# SDIO_WIFI.net
KiCad netlist of a schematic drawn in Altium Designer
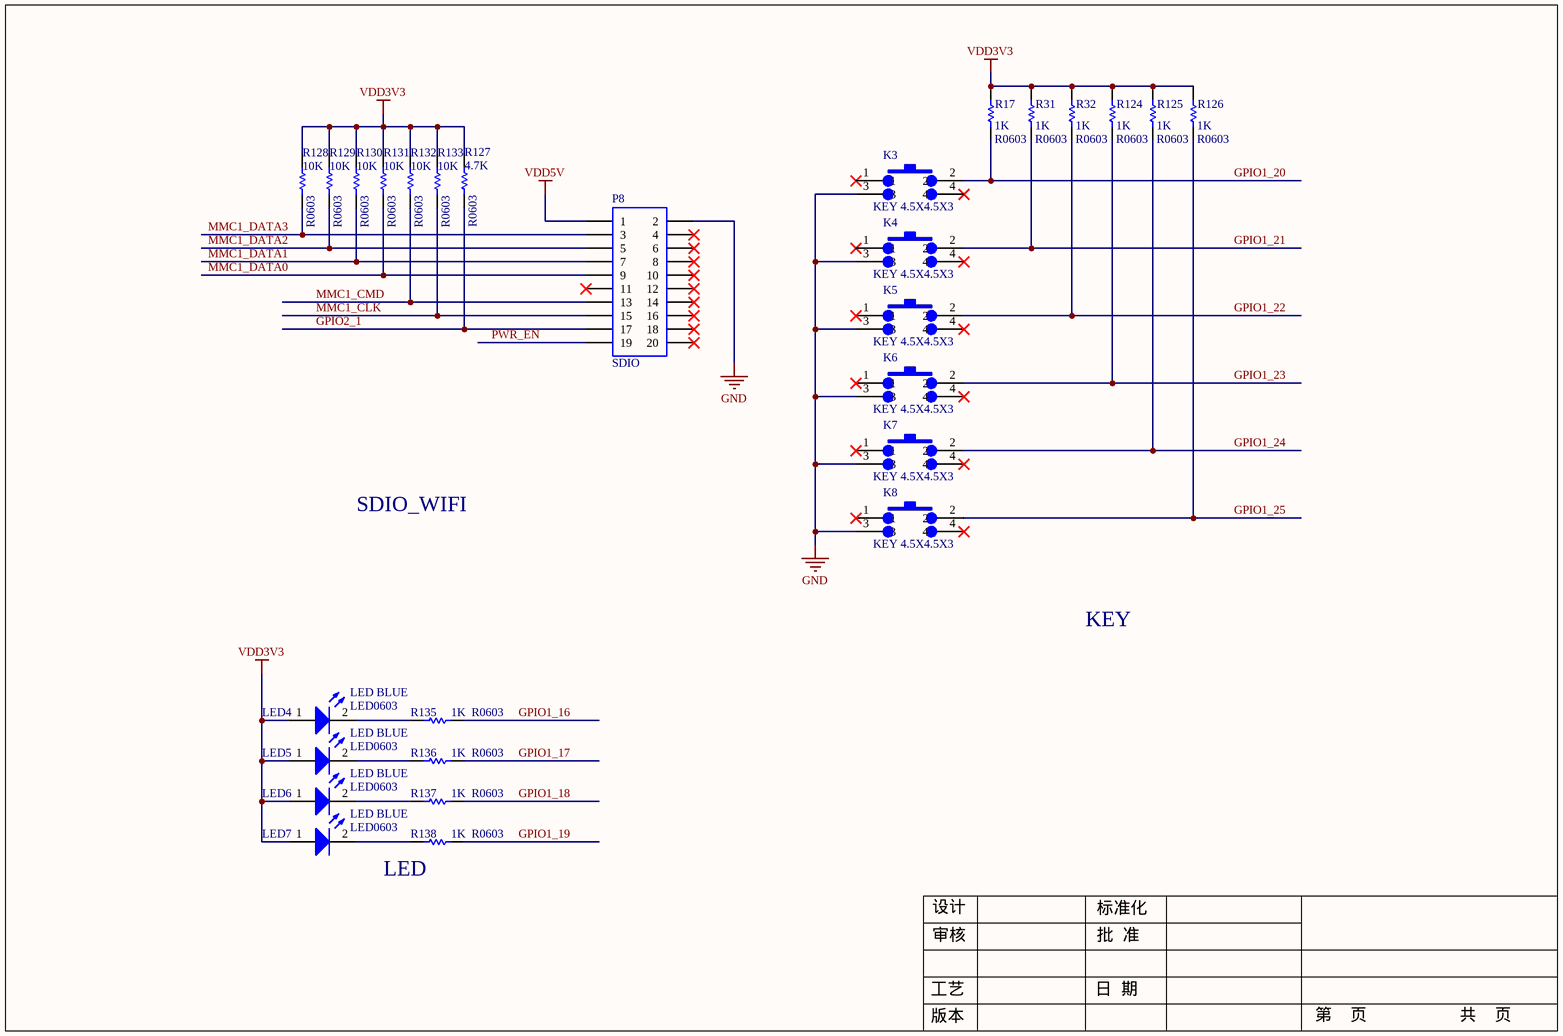
[diagram p0: SDIO_WIFI.SchDoc]

(export (version "E")
  (design (tool "Eeschema 10.0.6"))
  (components
    (comp (ref "K3")
      (value "KEY 4.5X4.5X3")
      (footprint "SWPB-4")
      (libsource (lib "AM335X_bottom") (part "KEY 4.5X4.5X3"))
    )
    (comp (ref "K4")
      (value "KEY 4.5X4.5X3")
      (footprint "SWPB-4")
      (libsource (lib "AM335X_bottom") (part "KEY 4.5X4.5X3"))
    )
    (comp (ref "K5")
      (value "KEY 4.5X4.5X3")
      (footprint "SWPB-4")
      (libsource (lib "AM335X_bottom") (part "KEY 4.5X4.5X3"))
    )
    (comp (ref "K6")
      (value "KEY 4.5X4.5X3")
      (footprint "SWPB-4")
      (libsource (lib "AM335X_bottom") (part "KEY 4.5X4.5X3"))
    )
    (comp (ref "K7")
      (value "KEY 4.5X4.5X3")
      (footprint "SWPB-4")
      (libsource (lib "AM335X_bottom") (part "KEY 4.5X4.5X3"))
    )
    (comp (ref "K8")
      (value "KEY 4.5X4.5X3")
      (footprint "SWPB-4")
      (libsource (lib "AM335X_bottom") (part "KEY 4.5X4.5X3"))
    )
    (comp (ref "LED4")
      (value "LED BLUE")
      (footprint "LED0603_M1608")
      (description "Typical RED, GREEN, YELLOW, AMBER GaAs LED")
      (fields (field (name "ALTIUM_VALUE") "LED0603") (field (name "PUBLISHER") "Altium Limited"))
      (libsource (lib "Miscellaneous Devices") (part "LED2"))
    )
    (comp (ref "LED5")
      (value "LED BLUE")
      (footprint "LED0603_M1608")
      (description "Typical RED, GREEN, YELLOW, AMBER GaAs LED")
      (fields (field (name "ALTIUM_VALUE") "LED0603") (field (name "PUBLISHER") "Altium Limited"))
      (libsource (lib "Miscellaneous Devices") (part "LED2"))
    )
    (comp (ref "LED6")
      (value "LED BLUE")
      (footprint "LED0603_M1608")
      (description "Typical RED, GREEN, YELLOW, AMBER GaAs LED")
      (fields (field (name "ALTIUM_VALUE") "LED0603") (field (name "PUBLISHER") "Altium Limited"))
      (libsource (lib "Miscellaneous Devices") (part "LED2"))
    )
    (comp (ref "LED7")
      (value "LED BLUE")
      (footprint "LED0603_M1608")
      (description "Typical RED, GREEN, YELLOW, AMBER GaAs LED")
      (fields (field (name "ALTIUM_VALUE") "LED0603") (field (name "PUBLISHER") "Altium Limited"))
      (libsource (lib "Miscellaneous Devices") (part "LED2"))
    )
    (comp (ref "P8")
      (value "SDIO")
      (footprint "IDC20S")
      (description "Header, 10-Pin, Dual row")
      (fields (field (name "PUBLISHER") "Altium Limited"))
      (libsource (lib "OK335xD") (part "Header 10X2"))
    )
    (comp (ref "R17")
      (value "1K")
      (footprint "R0603_M1608")
      (description "R0603")
      (fields (field (name "ALTIUM_VALUE") "R0603") (field (name "PUBLISHER") "Altium Limited"))
      (libsource (lib "Miscellaneous Devices") (part "Res1"))
    )
    (comp (ref "R31")
      (value "1K")
      (footprint "R0603_M1608")
      (description "R0603")
      (fields (field (name "ALTIUM_VALUE") "R0603") (field (name "PUBLISHER") "Altium Limited"))
      (libsource (lib "Miscellaneous Devices") (part "Res1"))
    )
    (comp (ref "R32")
      (value "1K")
      (footprint "R0603_M1608")
      (description "R0603")
      (fields (field (name "ALTIUM_VALUE") "R0603") (field (name "PUBLISHER") "Altium Limited"))
      (libsource (lib "Miscellaneous Devices") (part "Res1"))
    )
    (comp (ref "R124")
      (value "1K")
      (footprint "R0603_M1608")
      (description "R0603")
      (fields (field (name "ALTIUM_VALUE") "R0603") (field (name "PUBLISHER") "Altium Limited"))
      (libsource (lib "Miscellaneous Devices") (part "Res1"))
    )
    (comp (ref "R125")
      (value "1K")
      (footprint "R0603_M1608")
      (description "R0603")
      (fields (field (name "ALTIUM_VALUE") "R0603") (field (name "PUBLISHER") "Altium Limited"))
      (libsource (lib "Miscellaneous Devices") (part "Res1"))
    )
    (comp (ref "R126")
      (value "1K")
      (footprint "R0603_M1608")
      (description "R0603")
      (fields (field (name "ALTIUM_VALUE") "R0603") (field (name "PUBLISHER") "Altium Limited"))
      (libsource (lib "Miscellaneous Devices") (part "Res1"))
    )
    (comp (ref "R127")
      (value "4.7K")
      (footprint "R0603_M1608")
      (description "Resistor")
      (fields (field (name "ALTIUM_VALUE") "R0603") (field (name "PUBLISHER") "Altium Limited"))
      (libsource (lib "Miscellaneous Devices") (part "Res1"))
    )
    (comp (ref "R128")
      (value "10K")
      (footprint "R0603_M1608")
      (description "Resistor")
      (fields (field (name "ALTIUM_VALUE") "R0603") (field (name "PUBLISHER") "Altium Limited"))
      (libsource (lib "Miscellaneous Devices") (part "Res1"))
    )
    (comp (ref "R129")
      (value "10K")
      (footprint "R0603_M1608")
      (description "Resistor")
      (fields (field (name "ALTIUM_VALUE") "R0603") (field (name "PUBLISHER") "Altium Limited"))
      (libsource (lib "Miscellaneous Devices") (part "Res1"))
    )
    (comp (ref "R130")
      (value "10K")
      (footprint "R0603_M1608")
      (description "Resistor")
      (fields (field (name "ALTIUM_VALUE") "R0603") (field (name "PUBLISHER") "Altium Limited"))
      (libsource (lib "Miscellaneous Devices") (part "Res1"))
    )
    (comp (ref "R131")
      (value "10K")
      (footprint "R0603_M1608")
      (description "Resistor")
      (fields (field (name "ALTIUM_VALUE") "R0603") (field (name "PUBLISHER") "Altium Limited"))
      (libsource (lib "Miscellaneous Devices") (part "Res1"))
    )
    (comp (ref "R132")
      (value "10K")
      (footprint "R0603_M1608")
      (description "Resistor")
      (fields (field (name "ALTIUM_VALUE") "R0603") (field (name "PUBLISHER") "Altium Limited"))
      (libsource (lib "Miscellaneous Devices") (part "Res1"))
    )
    (comp (ref "R133")
      (value "10K")
      (footprint "R0603_M1608")
      (description "Resistor")
      (fields (field (name "ALTIUM_VALUE") "R0603") (field (name "PUBLISHER") "Altium Limited"))
      (libsource (lib "Miscellaneous Devices") (part "Res1"))
    )
    (comp (ref "R135")
      (value "1K")
      (footprint "R0603_M1608")
      (description "R0603")
      (fields (field (name "ALTIUM_VALUE") "R0603") (field (name "PUBLISHER") "Altium Limited"))
      (libsource (lib "Miscellaneous Devices") (part "Res1"))
    )
    (comp (ref "R136")
      (value "1K")
      (footprint "R0603_M1608")
      (description "R0603")
      (fields (field (name "ALTIUM_VALUE") "R0603") (field (name "PUBLISHER") "Altium Limited"))
      (libsource (lib "Miscellaneous Devices") (part "Res1"))
    )
    (comp (ref "R137")
      (value "1K")
      (footprint "R0603_M1608")
      (description "R0603")
      (fields (field (name "ALTIUM_VALUE") "R0603") (field (name "PUBLISHER") "Altium Limited"))
      (libsource (lib "Miscellaneous Devices") (part "Res1"))
    )
    (comp (ref "R138")
      (value "1K")
      (footprint "R0603_M1608")
      (description "R0603")
      (fields (field (name "ALTIUM_VALUE") "R0603") (field (name "PUBLISHER") "Altium Limited"))
      (libsource (lib "Miscellaneous Devices") (part "Res1"))
    )
  )
  (nets
    (net (code "1") (name "/GPIO1_16") (class "Default")
      (node (ref "R135") (pin "2") (pinfunction "2_2") (pintype "passive"))
    )
    (net (code "2") (name "/GPIO1_17") (class "Default")
      (node (ref "R136") (pin "2") (pinfunction "2_2") (pintype "passive"))
    )
    (net (code "3") (name "/GPIO1_18") (class "Default")
      (node (ref "R137") (pin "2") (pinfunction "2_2") (pintype "passive"))
    )
    (net (code "4") (name "/GPIO1_19") (class "Default")
      (node (ref "R138") (pin "2") (pinfunction "2_2") (pintype "passive"))
    )
    (net (code "5") (name "/GPIO1_20") (class "Default")
      (node (ref "K3") (pin "2") (pinfunction "2_2") (pintype "passive"))
      (node (ref "R17") (pin "2") (pinfunction "2_2") (pintype "passive"))
    )
    (net (code "6") (name "/GPIO1_21") (class "Default")
      (node (ref "K4") (pin "2") (pinfunction "2_2") (pintype "passive"))
      (node (ref "R31") (pin "2") (pinfunction "2_2") (pintype "passive"))
    )
    (net (code "7") (name "/GPIO1_22") (class "Default")
      (node (ref "K5") (pin "2") (pinfunction "2_2") (pintype "passive"))
      (node (ref "R32") (pin "2") (pinfunction "2_2") (pintype "passive"))
    )
    (net (code "8") (name "/GPIO1_23") (class "Default")
      (node (ref "K6") (pin "2") (pinfunction "2_2") (pintype "passive"))
      (node (ref "R124") (pin "2") (pinfunction "2_2") (pintype "passive"))
    )
    (net (code "9") (name "/GPIO1_24") (class "Default")
      (node (ref "K7") (pin "2") (pinfunction "2_2") (pintype "passive"))
      (node (ref "R125") (pin "2") (pinfunction "2_2") (pintype "passive"))
    )
    (net (code "10") (name "/GPIO1_25") (class "Default")
      (node (ref "K8") (pin "2") (pinfunction "2_2") (pintype "passive"))
      (node (ref "R126") (pin "2") (pinfunction "2_2") (pintype "passive"))
    )
    (net (code "11") (name "/GPIO2_1") (class "Default")
      (node (ref "P8") (pin "17") (pinfunction "17_17") (pintype "passive"))
      (node (ref "R127") (pin "2") (pinfunction "2_2") (pintype "passive"))
    )
    (net (code "12") (name "/MMC1_CLK") (class "Default")
      (node (ref "P8") (pin "15") (pinfunction "15_15") (pintype "passive"))
      (node (ref "R133") (pin "2") (pinfunction "2_2") (pintype "passive"))
    )
    (net (code "13") (name "/MMC1_CMD") (class "Default")
      (node (ref "P8") (pin "13") (pinfunction "13_13") (pintype "passive"))
      (node (ref "R132") (pin "2") (pinfunction "2_2") (pintype "passive"))
    )
    (net (code "14") (name "/MMC1_DATA0") (class "Default")
      (node (ref "P8") (pin "9") (pinfunction "9_9") (pintype "passive"))
      (node (ref "R131") (pin "2") (pinfunction "2_2") (pintype "passive"))
    )
    (net (code "15") (name "/MMC1_DATA1") (class "Default")
      (node (ref "P8") (pin "7") (pinfunction "7_7") (pintype "passive"))
      (node (ref "R130") (pin "2") (pinfunction "2_2") (pintype "passive"))
    )
    (net (code "16") (name "/MMC1_DATA2") (class "Default")
      (node (ref "P8") (pin "5") (pinfunction "5_5") (pintype "passive"))
      (node (ref "R129") (pin "2") (pinfunction "2_2") (pintype "passive"))
    )
    (net (code "17") (name "/MMC1_DATA3") (class "Default")
      (node (ref "P8") (pin "3") (pinfunction "3_3") (pintype "passive"))
      (node (ref "R128") (pin "2") (pinfunction "2_2") (pintype "passive"))
    )
    (net (code "18") (name "/PWR_EN") (class "Default")
      (node (ref "P8") (pin "19") (pinfunction "19_19") (pintype "passive"))
    )
    (net (code "19") (name "GND") (class "Default")
      (node (ref "K3") (pin "3") (pinfunction "3_3") (pintype "passive"))
      (node (ref "K4") (pin "3") (pinfunction "3_3") (pintype "passive"))
      (node (ref "K5") (pin "3") (pinfunction "3_3") (pintype "passive"))
      (node (ref "K6") (pin "3") (pinfunction "3_3") (pintype "passive"))
      (node (ref "K7") (pin "3") (pinfunction "3_3") (pintype "passive"))
      (node (ref "K8") (pin "3") (pinfunction "3_3") (pintype "passive"))
      (node (ref "P8") (pin "2") (pinfunction "2_2") (pintype "passive"))
    )
    (net (code "20") (name "Net-(LED4-K)") (class "Default")
      (node (ref "LED4") (pin "2") (pinfunction "K_2") (pintype "passive"))
      (node (ref "R135") (pin "1") (pinfunction "1_1") (pintype "passive"))
    )
    (net (code "21") (name "Net-(LED5-K)") (class "Default")
      (node (ref "LED5") (pin "2") (pinfunction "K_2") (pintype "passive"))
      (node (ref "R136") (pin "1") (pinfunction "1_1") (pintype "passive"))
    )
    (net (code "22") (name "Net-(LED6-K)") (class "Default")
      (node (ref "LED6") (pin "2") (pinfunction "K_2") (pintype "passive"))
      (node (ref "R137") (pin "1") (pinfunction "1_1") (pintype "passive"))
    )
    (net (code "23") (name "Net-(LED7-K)") (class "Default")
      (node (ref "LED7") (pin "2") (pinfunction "K_2") (pintype "passive"))
      (node (ref "R138") (pin "1") (pinfunction "1_1") (pintype "passive"))
    )
    (net (code "24") (name "VDD3V3") (class "Default")
      (node (ref "LED4") (pin "1") (pinfunction "A_1") (pintype "passive"))
      (node (ref "LED5") (pin "1") (pinfunction "A_1") (pintype "passive"))
      (node (ref "LED6") (pin "1") (pinfunction "A_1") (pintype "passive"))
      (node (ref "LED7") (pin "1") (pinfunction "A_1") (pintype "passive"))
      (node (ref "R124") (pin "1") (pinfunction "1_1") (pintype "passive"))
      (node (ref "R125") (pin "1") (pinfunction "1_1") (pintype "passive"))
      (node (ref "R126") (pin "1") (pinfunction "1_1") (pintype "passive"))
      (node (ref "R127") (pin "1") (pinfunction "1_1") (pintype "passive"))
      (node (ref "R128") (pin "1") (pinfunction "1_1") (pintype "passive"))
      (node (ref "R129") (pin "1") (pinfunction "1_1") (pintype "passive"))
      (node (ref "R130") (pin "1") (pinfunction "1_1") (pintype "passive"))
      (node (ref "R131") (pin "1") (pinfunction "1_1") (pintype "passive"))
      (node (ref "R132") (pin "1") (pinfunction "1_1") (pintype "passive"))
      (node (ref "R133") (pin "1") (pinfunction "1_1") (pintype "passive"))
      (node (ref "R17") (pin "1") (pinfunction "1_1") (pintype "passive"))
      (node (ref "R31") (pin "1") (pinfunction "1_1") (pintype "passive"))
      (node (ref "R32") (pin "1") (pinfunction "1_1") (pintype "passive"))
    )
    (net (code "25") (name "VDD5V") (class "Default")
      (node (ref "P8") (pin "1") (pinfunction "1_1") (pintype "passive"))
    )
    (net (code "26") (name "unconnected-(K3-Pad1)") (class "Default")
      (node (ref "K3") (pin "1") (pinfunction "1_1") (pintype "passive+no_connect"))
    )
    (net (code "27") (name "unconnected-(K3-Pad4)") (class "Default")
      (node (ref "K3") (pin "4") (pinfunction "4_4") (pintype "passive+no_connect"))
    )
    (net (code "28") (name "unconnected-(K4-Pad1)") (class "Default")
      (node (ref "K4") (pin "1") (pinfunction "1_1") (pintype "passive+no_connect"))
    )
    (net (code "29") (name "unconnected-(K4-Pad4)") (class "Default")
      (node (ref "K4") (pin "4") (pinfunction "4_4") (pintype "passive+no_connect"))
    )
    (net (code "30") (name "unconnected-(K5-Pad1)") (class "Default")
      (node (ref "K5") (pin "1") (pinfunction "1_1") (pintype "passive+no_connect"))
    )
    (net (code "31") (name "unconnected-(K5-Pad4)") (class "Default")
      (node (ref "K5") (pin "4") (pinfunction "4_4") (pintype "passive+no_connect"))
    )
    (net (code "32") (name "unconnected-(K6-Pad1)") (class "Default")
      (node (ref "K6") (pin "1") (pinfunction "1_1") (pintype "passive+no_connect"))
    )
    (net (code "33") (name "unconnected-(K6-Pad4)") (class "Default")
      (node (ref "K6") (pin "4") (pinfunction "4_4") (pintype "passive+no_connect"))
    )
    (net (code "34") (name "unconnected-(K7-Pad1)") (class "Default")
      (node (ref "K7") (pin "1") (pinfunction "1_1") (pintype "passive+no_connect"))
    )
    (net (code "35") (name "unconnected-(K7-Pad4)") (class "Default")
      (node (ref "K7") (pin "4") (pinfunction "4_4") (pintype "passive+no_connect"))
    )
    (net (code "36") (name "unconnected-(K8-Pad1)") (class "Default")
      (node (ref "K8") (pin "1") (pinfunction "1_1") (pintype "passive+no_connect"))
    )
    (net (code "37") (name "unconnected-(K8-Pad4)") (class "Default")
      (node (ref "K8") (pin "4") (pinfunction "4_4") (pintype "passive+no_connect"))
    )
    (net (code "38") (name "unconnected-(P8-Pad4)") (class "Default")
      (node (ref "P8") (pin "4") (pinfunction "4_4") (pintype "passive+no_connect"))
    )
    (net (code "39") (name "unconnected-(P8-Pad6)") (class "Default")
      (node (ref "P8") (pin "6") (pinfunction "6_6") (pintype "passive+no_connect"))
    )
    (net (code "40") (name "unconnected-(P8-Pad8)") (class "Default")
      (node (ref "P8") (pin "8") (pinfunction "8_8") (pintype "passive+no_connect"))
    )
    (net (code "41") (name "unconnected-(P8-Pad10)") (class "Default")
      (node (ref "P8") (pin "10") (pinfunction "10_10") (pintype "passive+no_connect"))
    )
    (net (code "42") (name "unconnected-(P8-Pad11)") (class "Default")
      (node (ref "P8") (pin "11") (pinfunction "11_11") (pintype "passive+no_connect"))
    )
    (net (code "43") (name "unconnected-(P8-Pad12)") (class "Default")
      (node (ref "P8") (pin "12") (pinfunction "12_12") (pintype "passive+no_connect"))
    )
    (net (code "44") (name "unconnected-(P8-Pad14)") (class "Default")
      (node (ref "P8") (pin "14") (pinfunction "14_14") (pintype "passive+no_connect"))
    )
    (net (code "45") (name "unconnected-(P8-Pad16)") (class "Default")
      (node (ref "P8") (pin "16") (pinfunction "16_16") (pintype "passive+no_connect"))
    )
    (net (code "46") (name "unconnected-(P8-Pad18)") (class "Default")
      (node (ref "P8") (pin "18") (pinfunction "18_18") (pintype "passive+no_connect"))
    )
    (net (code "47") (name "unconnected-(P8-Pad20)") (class "Default")
      (node (ref "P8") (pin "20") (pinfunction "20_20") (pintype "passive+no_connect"))
    )
  )
)
